# MCU.net
KiCad netlist of a schematic drawn in Altium Designer
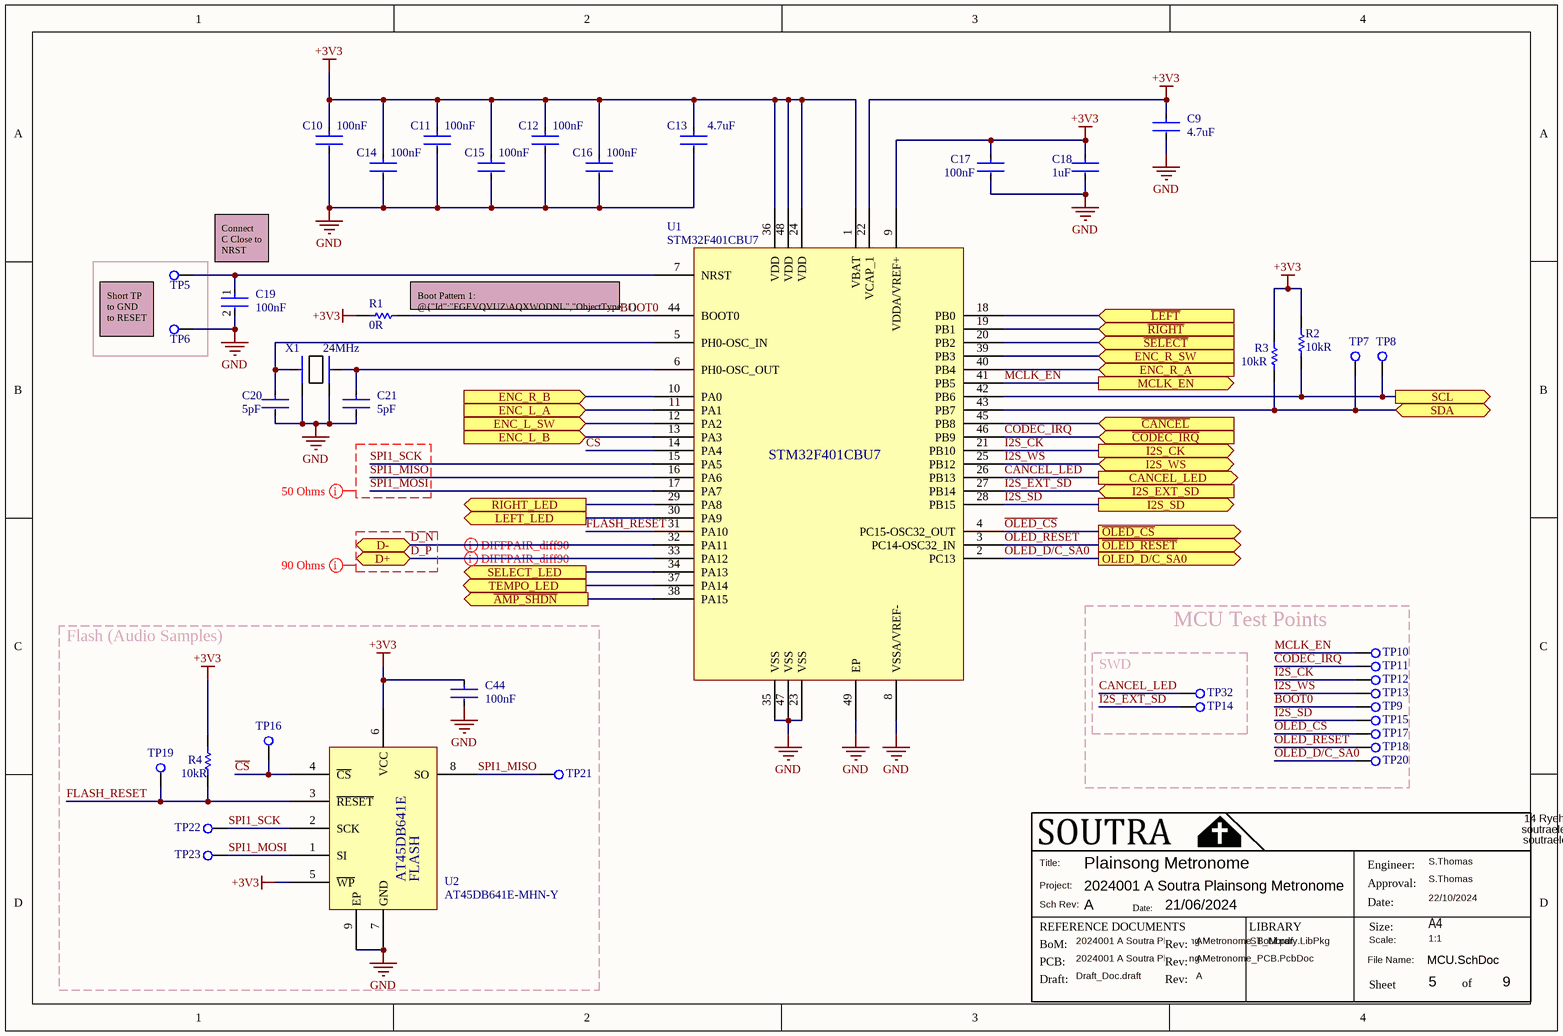
[diagram p0: MCU.SchDoc]

(export (version "E")
  (design (tool "Eeschema 10.0.6"))
  (components
    (comp (ref "C9")
      (value "4.7uF")
      (footprint "CC1206-IPC_A")
      (fields
        (field (name "MANUFACTURER") "Samsung")
        (field (name "MANUFACTURER PART NUMBER") "CL31B475KAHNNNE")
      )
      (libsource (lib "ST_Library") (part "CL31B475KAHNNNE"))
    )
    (comp (ref "C10")
      (value "100nF")
      (footprint "CAPC1005X06L")
      (fields
        (field (name "MANUFACTURER") "Walsin Technologies")
        (field (name "MANUFACTURER PART NUMBER") "0402X104M160CT")
        (field (name "ALTERNATIVE PART") "885012105016")
      )
      (libsource (lib "ST_Library") (part "0402X104M160CT"))
    )
    (comp (ref "C11")
      (value "100nF")
      (footprint "CAPC1005X06L")
      (fields
        (field (name "MANUFACTURER") "Walsin Technologies")
        (field (name "MANUFACTURER PART NUMBER") "0402X104M160CT")
        (field (name "ALTERNATIVE PART") "885012105016")
      )
      (libsource (lib "ST_Library") (part "0402X104M160CT"))
    )
    (comp (ref "C12")
      (value "100nF")
      (footprint "CAPC1005X06L")
      (fields
        (field (name "MANUFACTURER") "Walsin Technologies")
        (field (name "MANUFACTURER PART NUMBER") "0402X104M160CT")
        (field (name "ALTERNATIVE PART") "885012105016")
      )
      (libsource (lib "ST_Library") (part "0402X104M160CT"))
    )
    (comp (ref "C13")
      (value "4.7uF")
      (footprint "CC1206-IPC_A")
      (fields
        (field (name "MANUFACTURER") "Samsung")
        (field (name "MANUFACTURER PART NUMBER") "CL31B475KAHNNNE")
      )
      (libsource (lib "ST_Library") (part "CL31B475KAHNNNE"))
    )
    (comp (ref "C14")
      (value "100nF")
      (footprint "CAPC1005X06L")
      (fields
        (field (name "MANUFACTURER") "Walsin Technologies")
        (field (name "MANUFACTURER PART NUMBER") "0402X104M160CT")
        (field (name "ALTERNATIVE PART") "885012105016")
      )
      (libsource (lib "ST_Library") (part "0402X104M160CT"))
    )
    (comp (ref "C15")
      (value "100nF")
      (footprint "CAPC1005X06L")
      (fields
        (field (name "MANUFACTURER") "Walsin Technologies")
        (field (name "MANUFACTURER PART NUMBER") "0402X104M160CT")
        (field (name "ALTERNATIVE PART") "885012105016")
      )
      (libsource (lib "ST_Library") (part "0402X104M160CT"))
    )
    (comp (ref "C16")
      (value "100nF")
      (footprint "CAPC1005X06L")
      (fields
        (field (name "MANUFACTURER") "Walsin Technologies")
        (field (name "MANUFACTURER PART NUMBER") "0402X104M160CT")
        (field (name "ALTERNATIVE PART") "885012105016")
      )
      (libsource (lib "ST_Library") (part "0402X104M160CT"))
    )
    (comp (ref "C17")
      (value "100nF")
      (footprint "CAPC1005X06L")
      (fields
        (field (name "MANUFACTURER") "Walsin Technologies")
        (field (name "MANUFACTURER PART NUMBER") "0402X104M160CT")
        (field (name "ALTERNATIVE PART") "885012105016")
      )
      (libsource (lib "ST_Library") (part "0402X104M160CT"))
    )
    (comp (ref "C18")
      (value "1uF")
      (footprint "CAPC1005X06L")
      (fields
        (field (name "MANUFACTURER") "Yageo")
        (field (name "MANUFACTURER PART NUMBER") "CC0402KRX5R6BB105")
        (field (name "ALTERNATIVE PART") "0402ZD105KAT2A")
      )
      (libsource (lib "ST_Library") (part "CC0402KRX5R6BB105"))
    )
    (comp (ref "C19")
      (value "100nF")
      (footprint "CAPC1005X06L")
      (fields
        (field (name "MANUFACTURER") "Walsin Technologies")
        (field (name "MANUFACTURER PART NUMBER") "0402X104M160CT")
        (field (name "ALTERNATIVE PART") "885012105016")
      )
      (libsource (lib "") (part "0402X104M160CT_1"))
    )
    (comp (ref "C20")
      (value "5pF")
      (footprint "CAPC1005X06L")
      (fields
        (field (name "MANUFACTURER") "Yageo")
        (field (name "MANUFACTURER PART NUMBER") "CC0402CRNPO9BN5R0")
        (field (name "ALTERNATIVE PART") "GJM1555C1H5R0CB01D")
      )
      (libsource (lib "ST_Library") (part "CC0402CRNPO9BN5R0"))
    )
    (comp (ref "C21")
      (value "5pF")
      (footprint "CAPC1005X06L")
      (fields
        (field (name "MANUFACTURER") "Yageo")
        (field (name "MANUFACTURER PART NUMBER") "CC0402CRNPO9BN5R0")
        (field (name "ALTERNATIVE PART") "GJM1555C1H5R0CB01D")
      )
      (libsource (lib "ST_Library") (part "CC0402CRNPO9BN5R0"))
    )
    (comp (ref "C44")
      (value "100nF")
      (footprint "CAPC1005X06L")
      (fields
        (field (name "MANUFACTURER") "Walsin Technologies")
        (field (name "MANUFACTURER PART NUMBER") "0402X104M160CT")
        (field (name "ALTERNATIVE PART") "885012105016")
      )
      (libsource (lib "ST_Library") (part "0402X104M160CT"))
    )
    (comp (ref "R1")
      (value "0R")
      (footprint "RESC_0603_1608X06L")
      (description "Fixed Resistor, Metal Glaze/thick Film, 0.063W, 0ohm, 1% +/-Tol, Surface Mount, 0603")
      (fields
        (field (name "MANUFACTURER") "Multicomp")
        (field (name "MANUFACTURER PART NUMBER") "MC0063W06030R")
      )
      (libsource (lib "ST_Library") (part "MC0063W06030R"))
    )
    (comp (ref "R2")
      (value "10kR")
      (footprint "RESC_0603_1608X06L")
      (fields
        (field (name "MANUFACTURER") "KOA Speer")
        (field (name "MANUFACTURER PART NUMBER") "RK73B1JTTD103J")
        (field (name "TOLERANCE") "5%")
      )
      (libsource (lib "ST_Library") (part "RK73B1JTTD103J"))
    )
    (comp (ref "R3")
      (value "10kR")
      (footprint "RESC_0603_1608X06L")
      (fields
        (field (name "MANUFACTURER") "KOA Speer")
        (field (name "MANUFACTURER PART NUMBER") "RK73B1JTTD103J")
        (field (name "TOLERANCE") "5%")
      )
      (libsource (lib "ST_Library") (part "RK73B1JTTD103J"))
    )
    (comp (ref "R4")
      (value "10kR")
      (footprint "RESC_0805_2013X50X30LL20T20")
      (fields
        (field (name "MANUFACTURER") "Yageo")
        (field (name "MANUFACTURER PART NUMBER") "RC0805JR-0710KL")
        (field (name "TOLERANCE") "5%")
      )
      (libsource (lib "ST_Library") (part "RC0805JR-0710KL"))
    )
    (comp (ref "TP5")
      (value "TP_CIRCLE_R1")
      (footprint "TP_CIRCLE_R1")
      (description "Test Point, SMD, Circular, Radius = 1mm")
      (libsource (lib "ST_Library") (part "TP_CIRCLE_R1"))
    )
    (comp (ref "TP6")
      (value "TP_CIRCLE_R1")
      (footprint "TP_CIRCLE_R1")
      (description "Test Point, SMD, Circular, Radius = 1mm")
      (libsource (lib "ST_Library") (part "TP_CIRCLE_R1"))
    )
    (comp (ref "TP7")
      (value "TP_CIRCLE_R1")
      (footprint "TP_CIRCLE_R1")
      (description "Test Point, SMD, Circular, Radius = 1mm")
      (libsource (lib "ST_Library") (part "TP_CIRCLE_R1"))
    )
    (comp (ref "TP8")
      (value "TP_CIRCLE_R1")
      (footprint "TP_CIRCLE_R1")
      (description "Test Point, SMD, Circular, Radius = 1mm")
      (libsource (lib "ST_Library") (part "TP_CIRCLE_R1"))
    )
    (comp (ref "TP9")
      (value "TP_CIRCLE_R1")
      (footprint "TP_CIRCLE_R1")
      (description "Test Point, SMD, Circular, Radius = 1mm")
      (libsource (lib "ST_Library") (part "TP_CIRCLE_R1"))
    )
    (comp (ref "TP10")
      (value "TP_CIRCLE_R1")
      (footprint "TP_CIRCLE_R1")
      (description "Test Point, SMD, Circular, Radius = 1mm")
      (libsource (lib "ST_Library") (part "TP_CIRCLE_R1"))
    )
    (comp (ref "TP11")
      (value "TP_CIRCLE_R1")
      (footprint "TP_CIRCLE_R1")
      (description "Test Point, SMD, Circular, Radius = 1mm")
      (libsource (lib "ST_Library") (part "TP_CIRCLE_R1"))
    )
    (comp (ref "TP12")
      (value "TP_CIRCLE_R1")
      (footprint "TP_CIRCLE_R1")
      (description "Test Point, SMD, Circular, Radius = 1mm")
      (libsource (lib "ST_Library") (part "TP_CIRCLE_R1"))
    )
    (comp (ref "TP13")
      (value "TP_CIRCLE_R1")
      (footprint "TP_CIRCLE_R1")
      (description "Test Point, SMD, Circular, Radius = 1mm")
      (libsource (lib "ST_Library") (part "TP_CIRCLE_R1"))
    )
    (comp (ref "TP14")
      (value "TP_CIRCLE_R1")
      (footprint "TP_CIRCLE_R1")
      (description "Test Point, SMD, Circular, Radius = 1mm")
      (libsource (lib "ST_Library") (part "TP_CIRCLE_R1"))
    )
    (comp (ref "TP15")
      (value "TP_CIRCLE_R1")
      (footprint "TP_CIRCLE_R1")
      (description "Test Point, SMD, Circular, Radius = 1mm")
      (libsource (lib "ST_Library") (part "TP_CIRCLE_R1"))
    )
    (comp (ref "TP16")
      (value "TP_CIRCLE_R1")
      (footprint "TP_CIRCLE_R1")
      (description "Test Point, SMD, Circular, Radius = 1mm")
      (libsource (lib "ST_Library") (part "TP_CIRCLE_R1"))
    )
    (comp (ref "TP17")
      (value "TP_CIRCLE_R1")
      (footprint "TP_CIRCLE_R1")
      (description "Test Point, SMD, Circular, Radius = 1mm")
      (libsource (lib "ST_Library") (part "TP_CIRCLE_R1"))
    )
    (comp (ref "TP18")
      (value "TP_CIRCLE_R1")
      (footprint "TP_CIRCLE_R1")
      (description "Test Point, SMD, Circular, Radius = 1mm")
      (libsource (lib "ST_Library") (part "TP_CIRCLE_R1"))
    )
    (comp (ref "TP19")
      (value "TP_CIRCLE_R1")
      (footprint "TP_CIRCLE_R1")
      (description "Test Point, SMD, Circular, Radius = 1mm")
      (libsource (lib "ST_Library") (part "TP_CIRCLE_R1"))
    )
    (comp (ref "TP20")
      (value "TP_CIRCLE_R1")
      (footprint "TP_CIRCLE_R1")
      (description "Test Point, SMD, Circular, Radius = 1mm")
      (libsource (lib "ST_Library") (part "TP_CIRCLE_R1"))
    )
    (comp (ref "TP21")
      (value "TP_CIRCLE_R1")
      (footprint "TP_CIRCLE_R1")
      (description "Test Point, SMD, Circular, Radius = 1mm")
      (libsource (lib "ST_Library") (part "TP_CIRCLE_R1"))
    )
    (comp (ref "TP22")
      (value "TP_CIRCLE_R1")
      (footprint "TP_CIRCLE_R1")
      (description "Test Point, SMD, Circular, Radius = 1mm")
      (libsource (lib "ST_Library") (part "TP_CIRCLE_R1"))
    )
    (comp (ref "TP23")
      (value "TP_CIRCLE_R1")
      (footprint "TP_CIRCLE_R1")
      (description "Test Point, SMD, Circular, Radius = 1mm")
      (libsource (lib "ST_Library") (part "TP_CIRCLE_R1"))
    )
    (comp (ref "TP32")
      (value "TP_CIRCLE_R1")
      (footprint "TP_CIRCLE_R1")
      (description "Test Point, SMD, Circular, Radius = 1mm")
      (libsource (lib "ST_Library") (part "TP_CIRCLE_R1"))
    )
    (comp (ref "U1")
      (value "STM32F401CBU7")
      (footprint "UFQFPN50P700X700X60_HS-49L")
      (description "RISC Microcontroller, 32-Bit, FLASH, 84MHz, CMOS")
      (fields (field (name "MANUFACTURER") "STMicroelectronics"))
      (libsource (lib "ST_Library") (part "STM32F401CBU7"))
    )
    (comp (ref "U2")
      (value "AT45DB641E-MHN-Y")
      (footprint "QFN127P600X500X60_HS-9L")
      (description "Flash, 64MX1, PDSO8")
      (fields (field (name "MANUFACTURER") "Adesto Technologies"))
      (libsource (lib "ST_Library") (part "AT45DB641E-MHN-Y"))
    )
    (comp (ref "X1")
      (value "24MHz")
      (footprint "OSCSC1-85x1-55P2-55X2-05Y0-05_4MFR")
      (description "Parallel - Fundamental Quartz Crystal")
      (fields
        (field (name "MANUFACTURER") "Multicomp")
        (field (name "MANUFACTURER PART NUMBER") "MCSJK-7E-24.00-8-10-60-B-10")
      )
      (libsource (lib "ST_Library") (part "MCSJK-7E-24.00-8-10-60-B-10"))
    )
  )
  (nets
    (net (code "1") (name "+3V3") (class "Default")
      (node (ref "C10") (pin "1") (pinfunction "1_1") (pintype "passive"))
      (node (ref "C11") (pin "1") (pinfunction "1_1") (pintype "passive"))
      (node (ref "C12") (pin "1") (pinfunction "1_1") (pintype "passive"))
      (node (ref "C13") (pin "1") (pinfunction "1_1") (pintype "passive"))
      (node (ref "C14") (pin "1") (pinfunction "1_1") (pintype "passive"))
      (node (ref "C15") (pin "1") (pinfunction "1_1") (pintype "passive"))
      (node (ref "C16") (pin "1") (pinfunction "1_1") (pintype "passive"))
      (node (ref "C17") (pin "1") (pinfunction "1_1") (pintype "passive"))
      (node (ref "C18") (pin "1") (pinfunction "1_1") (pintype "passive"))
      (node (ref "C44") (pin "1") (pinfunction "1_1") (pintype "passive"))
      (node (ref "C9") (pin "1") (pinfunction "1_1") (pintype "passive"))
      (node (ref "R1") (pin "2") (pinfunction "2_2") (pintype "passive"))
      (node (ref "R2") (pin "2") (pinfunction "2_2") (pintype "passive"))
      (node (ref "R3") (pin "2") (pinfunction "2_2") (pintype "passive"))
      (node (ref "R4") (pin "2") (pinfunction "2_2") (pintype "passive"))
      (node (ref "U1") (pin "1") (pinfunction "VBAT_1") (pintype "passive"))
      (node (ref "U1") (pin "22") (pinfunction "VCAP_1_22") (pintype "passive"))
      (node (ref "U1") (pin "24") (pinfunction "VDD_24") (pintype "passive"))
      (node (ref "U1") (pin "36") (pinfunction "VDD_36") (pintype "passive"))
      (node (ref "U1") (pin "48") (pinfunction "VDD_48") (pintype "passive"))
      (node (ref "U1") (pin "9") (pinfunction "VDDA/VREF+_9") (pintype "passive"))
      (node (ref "U2") (pin "5") (pinfunction "~{WP}_5") (pintype "passive"))
      (node (ref "U2") (pin "6") (pinfunction "VCC_6") (pintype "passive"))
    )
    (net (code "2") (name "/BOOT0") (class "Default")
      (node (ref "R1") (pin "1") (pinfunction "1_1") (pintype "passive"))
      (node (ref "TP9") (pin "1") (pinfunction "1_1") (pintype "passive"))
      (node (ref "U1") (pin "44") (pinfunction "BOOT0_44") (pintype "passive"))
    )
    (net (code "3") (name "/CANCEL_LED") (class "Default")
      (node (ref "TP32") (pin "1") (pinfunction "1_1") (pintype "passive"))
      (node (ref "U1") (pin "26") (pinfunction "PB13_26") (pintype "passive"))
    )
    (net (code "4") (name "/D_N") (class "Default")
      (node (ref "U1") (pin "32") (pinfunction "PA11_32") (pintype "passive"))
    )
    (net (code "5") (name "/D_P") (class "Default")
      (node (ref "U1") (pin "33") (pinfunction "PA12_33") (pintype "passive"))
    )
    (net (code "6") (name "/ENC_L_A") (class "Default")
      (node (ref "U1") (pin "11") (pinfunction "PA1_11") (pintype "passive"))
    )
    (net (code "7") (name "/ENC_L_B") (class "Default")
      (node (ref "U1") (pin "13") (pinfunction "PA3_13") (pintype "passive"))
    )
    (net (code "8") (name "/ENC_L_SW") (class "Default")
      (node (ref "U1") (pin "12") (pinfunction "PA2_12") (pintype "passive"))
    )
    (net (code "9") (name "/ENC_R_A") (class "Default")
      (node (ref "U1") (pin "40") (pinfunction "PB4_40") (pintype "passive"))
    )
    (net (code "10") (name "/ENC_R_B") (class "Default")
      (node (ref "U1") (pin "10") (pinfunction "PA0_10") (pintype "passive"))
    )
    (net (code "11") (name "/ENC_R_SW") (class "Default")
      (node (ref "U1") (pin "39") (pinfunction "PB3_39") (pintype "passive"))
    )
    (net (code "12") (name "/FLASH_RESET") (class "Default")
      (node (ref "R4") (pin "1") (pinfunction "1_1") (pintype "passive"))
      (node (ref "TP19") (pin "1") (pinfunction "1_1") (pintype "passive"))
      (node (ref "U1") (pin "31") (pinfunction "PA10_31") (pintype "passive"))
      (node (ref "U2") (pin "3") (pinfunction "~{RESET}_3") (pintype "passive"))
    )
    (net (code "13") (name "/I2S_CK") (class "Default")
      (node (ref "TP12") (pin "1") (pinfunction "1_1") (pintype "passive"))
      (node (ref "U1") (pin "21") (pinfunction "PB10_21") (pintype "passive"))
    )
    (net (code "14") (name "/I2S_EXT_SD") (class "Default")
      (node (ref "TP14") (pin "1") (pinfunction "1_1") (pintype "passive"))
      (node (ref "U1") (pin "27") (pinfunction "PB14_27") (pintype "passive"))
    )
    (net (code "15") (name "/I2S_SD") (class "Default")
      (node (ref "TP15") (pin "1") (pinfunction "1_1") (pintype "passive"))
      (node (ref "U1") (pin "28") (pinfunction "PB15_28") (pintype "passive"))
    )
    (net (code "16") (name "/I2S_WS") (class "Default")
      (node (ref "TP13") (pin "1") (pinfunction "1_1") (pintype "passive"))
      (node (ref "U1") (pin "25") (pinfunction "PB12_25") (pintype "passive"))
    )
    (net (code "17") (name "/LEFT_LED") (class "Default")
      (node (ref "U1") (pin "30") (pinfunction "PA9_30") (pintype "passive"))
    )
    (net (code "18") (name "/MCLK_EN") (class "Default")
      (node (ref "TP10") (pin "1") (pinfunction "1_1") (pintype "passive"))
      (node (ref "U1") (pin "41") (pinfunction "PB5_41") (pintype "passive"))
    )
    (net (code "19") (name "/OLED_D{slash}C_SA0") (class "Default")
      (node (ref "TP20") (pin "1") (pinfunction "1_1") (pintype "passive"))
      (node (ref "U1") (pin "2") (pinfunction "PC13_2") (pintype "passive"))
    )
    (net (code "20") (name "/RIGHT_LED") (class "Default")
      (node (ref "U1") (pin "29") (pinfunction "PA8_29") (pintype "passive"))
    )
    (net (code "21") (name "/SCL") (class "Default")
      (node (ref "R2") (pin "1") (pinfunction "1_1") (pintype "passive"))
      (node (ref "TP8") (pin "1") (pinfunction "1_1") (pintype "passive"))
      (node (ref "U1") (pin "42") (pinfunction "PB6_42") (pintype "passive"))
    )
    (net (code "22") (name "/SDA") (class "Default")
      (node (ref "R3") (pin "1") (pinfunction "1_1") (pintype "passive"))
      (node (ref "TP7") (pin "1") (pinfunction "1_1") (pintype "passive"))
      (node (ref "U1") (pin "43") (pinfunction "PB7_43") (pintype "passive"))
    )
    (net (code "23") (name "/SELECT_LED") (class "Default")
      (node (ref "U1") (pin "34") (pinfunction "PA13_34") (pintype "passive"))
    )
    (net (code "24") (name "/SPI1_MISO") (class "Default")
      (node (ref "TP21") (pin "1") (pinfunction "1_1") (pintype "passive"))
      (node (ref "U1") (pin "16") (pinfunction "PA6_16") (pintype "passive"))
      (node (ref "U2") (pin "8") (pinfunction "SO_8") (pintype "passive"))
    )
    (net (code "25") (name "/SPI1_MOSI") (class "Default")
      (node (ref "TP23") (pin "1") (pinfunction "1_1") (pintype "passive"))
      (node (ref "U1") (pin "17") (pinfunction "PA7_17") (pintype "passive"))
      (node (ref "U2") (pin "1") (pinfunction "SI_1") (pintype "passive"))
    )
    (net (code "26") (name "/SPI1_SCK") (class "Default")
      (node (ref "TP22") (pin "1") (pinfunction "1_1") (pintype "passive"))
      (node (ref "U1") (pin "15") (pinfunction "PA5_15") (pintype "passive"))
      (node (ref "U2") (pin "2") (pinfunction "SCK_2") (pintype "passive"))
    )
    (net (code "27") (name "/TEMPO_LED") (class "Default")
      (node (ref "U1") (pin "37") (pinfunction "PA14_37") (pintype "passive"))
    )
    (net (code "28") (name "/~{AMP_SHDN}") (class "Default")
      (node (ref "U1") (pin "38") (pinfunction "PA15_38") (pintype "passive"))
    )
    (net (code "29") (name "/~{CANCEL}") (class "Default")
      (node (ref "U1") (pin "45") (pinfunction "PB8_45") (pintype "passive"))
    )
    (net (code "30") (name "/~{CODEC_IRQ}") (class "Default")
      (node (ref "TP11") (pin "1") (pinfunction "1_1") (pintype "passive"))
      (node (ref "U1") (pin "46") (pinfunction "PB9_46") (pintype "passive"))
    )
    (net (code "31") (name "/~{CS}") (class "Default")
      (node (ref "TP16") (pin "1") (pinfunction "1_1") (pintype "passive"))
      (node (ref "U1") (pin "14") (pinfunction "PA4_14") (pintype "passive"))
      (node (ref "U2") (pin "4") (pinfunction "~{CS}_4") (pintype "passive"))
    )
    (net (code "32") (name "/~{LEFT}") (class "Default")
      (node (ref "U1") (pin "18") (pinfunction "PB0_18") (pintype "passive"))
    )
    (net (code "33") (name "/~{OLED_CS}") (class "Default")
      (node (ref "TP17") (pin "1") (pinfunction "1_1") (pintype "passive"))
      (node (ref "U1") (pin "4") (pinfunction "PC15-OSC32_OUT_4") (pintype "passive"))
    )
    (net (code "34") (name "/~{OLED_RESET}") (class "Default")
      (node (ref "TP18") (pin "1") (pinfunction "1_1") (pintype "passive"))
      (node (ref "U1") (pin "3") (pinfunction "PC14-OSC32_IN_3") (pintype "passive"))
    )
    (net (code "35") (name "/~{RIGHT}") (class "Default")
      (node (ref "U1") (pin "19") (pinfunction "PB1_19") (pintype "passive"))
    )
    (net (code "36") (name "/~{SELECT}") (class "Default")
      (node (ref "U1") (pin "20") (pinfunction "PB2_20") (pintype "passive"))
    )
    (net (code "37") (name "GND") (class "Default")
      (node (ref "C10") (pin "2") (pinfunction "2_2") (pintype "passive"))
      (node (ref "C11") (pin "2") (pinfunction "2_2") (pintype "passive"))
      (node (ref "C12") (pin "2") (pinfunction "2_2") (pintype "passive"))
      (node (ref "C13") (pin "2") (pinfunction "2_2") (pintype "passive"))
      (node (ref "C14") (pin "2") (pinfunction "2_2") (pintype "passive"))
      (node (ref "C15") (pin "2") (pinfunction "2_2") (pintype "passive"))
      (node (ref "C16") (pin "2") (pinfunction "2_2") (pintype "passive"))
      (node (ref "C17") (pin "2") (pinfunction "2_2") (pintype "passive"))
      (node (ref "C18") (pin "2") (pinfunction "2_2") (pintype "passive"))
      (node (ref "C19") (pin "2") (pinfunction "2_2") (pintype "passive"))
      (node (ref "C20") (pin "2") (pinfunction "2_2") (pintype "passive"))
      (node (ref "C21") (pin "2") (pinfunction "2_2") (pintype "passive"))
      (node (ref "C44") (pin "2") (pinfunction "2_2") (pintype "passive"))
      (node (ref "C9") (pin "2") (pinfunction "2_2") (pintype "passive"))
      (node (ref "TP6") (pin "1") (pinfunction "1_1") (pintype "passive"))
      (node (ref "U1") (pin "23") (pinfunction "VSS_23") (pintype "passive"))
      (node (ref "U1") (pin "35") (pinfunction "VSS_35") (pintype "passive"))
      (node (ref "U1") (pin "47") (pinfunction "VSS_47") (pintype "passive"))
      (node (ref "U1") (pin "49") (pinfunction "EP_49") (pintype "passive"))
      (node (ref "U1") (pin "8") (pinfunction "VSSA/VREF-_8") (pintype "passive"))
      (node (ref "U2") (pin "7") (pinfunction "GND_7") (pintype "passive"))
      (node (ref "U2") (pin "9") (pinfunction "EP_9") (pintype "passive"))
      (node (ref "X1") (pin "2") (pinfunction "2_2") (pintype "passive"))
      (node (ref "X1") (pin "4") (pinfunction "4_4") (pintype "passive"))
    )
    (net (code "38") (name "Net-(U1-NRST)") (class "Default")
      (node (ref "C19") (pin "1") (pinfunction "1_1") (pintype "passive"))
      (node (ref "TP5") (pin "1") (pinfunction "1_1") (pintype "passive"))
      (node (ref "U1") (pin "7") (pinfunction "NRST_7") (pintype "passive"))
    )
    (net (code "39") (name "Net-(U1-PH0-OSC_IN)") (class "Default")
      (node (ref "C20") (pin "1") (pinfunction "1_1") (pintype "passive"))
      (node (ref "U1") (pin "5") (pinfunction "PH0-OSC_IN_5") (pintype "passive"))
      (node (ref "X1") (pin "1") (pinfunction "1_1") (pintype "passive"))
    )
    (net (code "40") (name "Net-(U1-PH0-OSC_OUT)") (class "Default")
      (node (ref "C21") (pin "1") (pinfunction "1_1") (pintype "passive"))
      (node (ref "U1") (pin "6") (pinfunction "PH0-OSC_OUT_6") (pintype "passive"))
      (node (ref "X1") (pin "3") (pinfunction "3_3") (pintype "passive"))
    )
  )
)
